# Power.net
KiCad netlist of a schematic drawn in Altium Designer
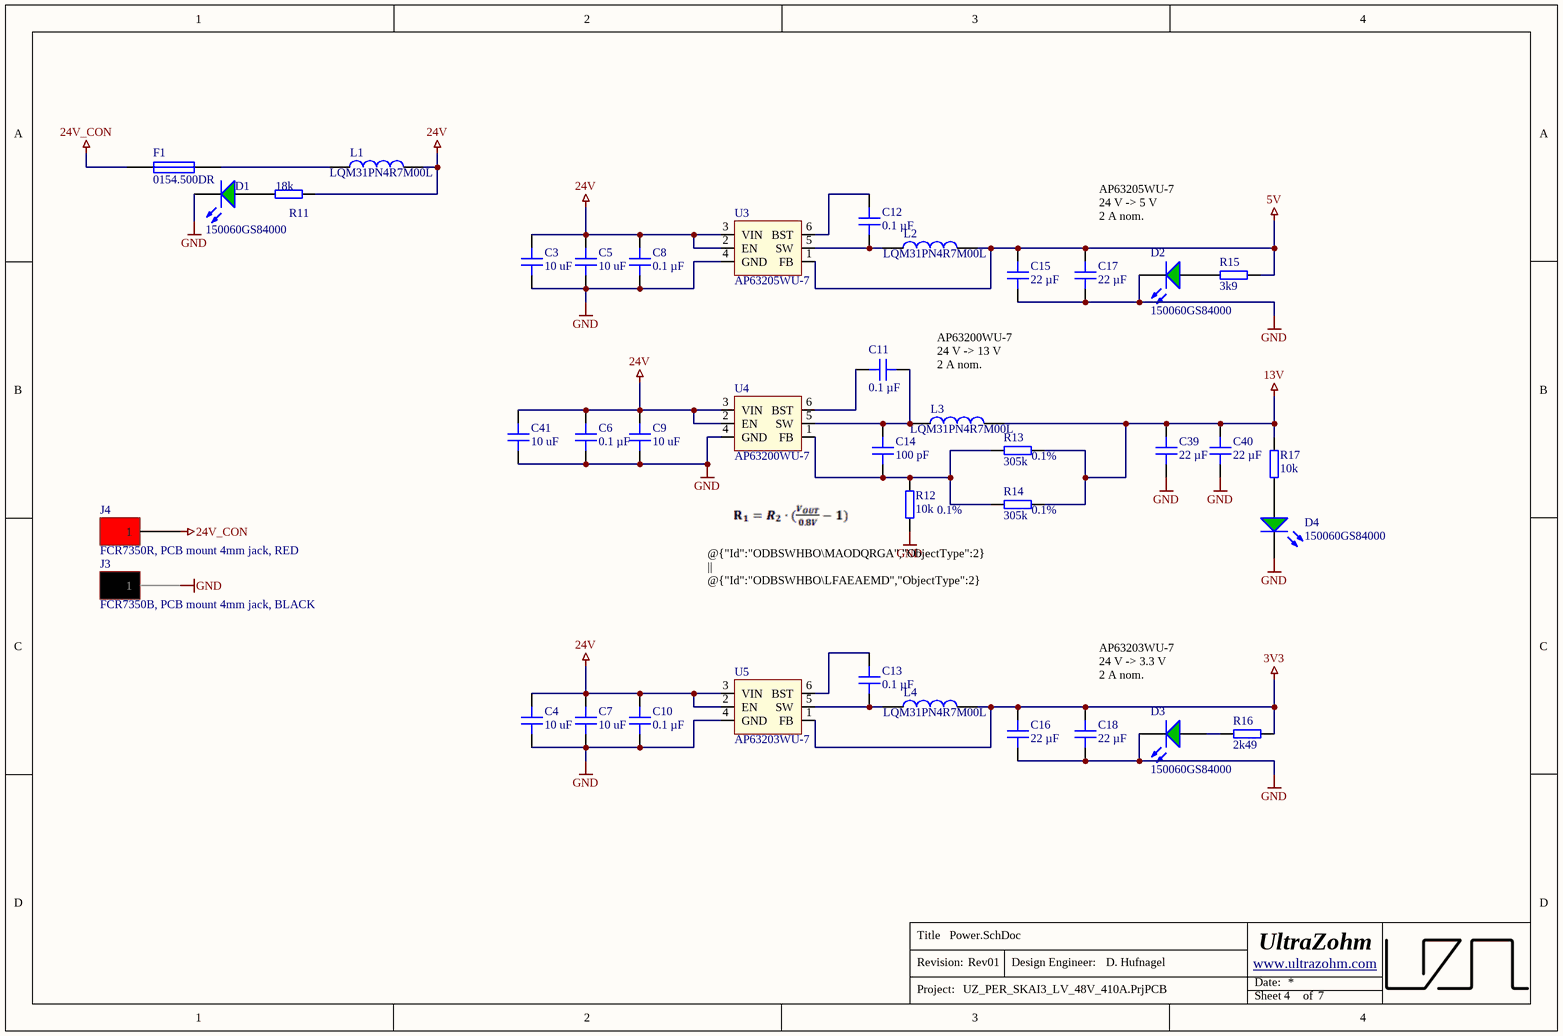
[diagram p0: Power.SchDoc]

(export (version "E")
  (design (tool "Eeschema 10.0.6"))
  (components
    (comp (ref "C3")
      (value "10 uF")
      (footprint "C_1206")
      (description "50V 10uF X7R ±10% 1206  Multilayer Ceramic Capacitors MLCC - SMD/SMT ROHS")
      (fields
        (field (name "MANUFACTURER PART NUMBER") "CL31B106KBHNNNE")
        (field (name "MANUFACTURER") "Samsung Electro-Mechanics")
        (field (name "CREATED FROM") "AGeiger")
      )
      (libsource (lib "user") (part "Capacitor"))
    )
    (comp (ref "C4")
      (value "10 uF")
      (footprint "C_1206")
      (description "50V 10uF X7R ±10% 1206  Multilayer Ceramic Capacitors MLCC - SMD/SMT ROHS")
      (fields
        (field (name "MANUFACTURER PART NUMBER") "CL31B106KBHNNNE")
        (field (name "MANUFACTURER") "Samsung Electro-Mechanics")
        (field (name "CREATED FROM") "AGeiger")
      )
      (libsource (lib "user") (part "Capacitor"))
    )
    (comp (ref "C5")
      (value "10 uF")
      (footprint "C_1206")
      (description "50V 10uF X7R ±10% 1206  Multilayer Ceramic Capacitors MLCC - SMD/SMT ROHS")
      (fields
        (field (name "MANUFACTURER PART NUMBER") "CL31B106KBHNNNE")
        (field (name "MANUFACTURER") "Samsung Electro-Mechanics")
        (field (name "CREATED FROM") "AGeiger")
      )
      (libsource (lib "user") (part "Capacitor"))
    )
    (comp (ref "C6")
      (value "0.1 µF")
      (footprint "C_0603")
      (description "Capacitor 0603, 50 VDC, 0.1 µF, X7R")
      (fields
        (field (name "MANUFACTURER PART NUMBER") "C0603X104K5RAC7411")
        (field (name "MANUFACTURER") "KEMET")
        (field (name "CREATED FROM") "MGremer")
      )
      (libsource (lib "user") (part "Capacitor"))
    )
    (comp (ref "C7")
      (value "10 uF")
      (footprint "C_1206")
      (description "50V 10uF X7R ±10% 1206  Multilayer Ceramic Capacitors MLCC - SMD/SMT ROHS")
      (fields
        (field (name "MANUFACTURER PART NUMBER") "CL31B106KBHNNNE")
        (field (name "MANUFACTURER") "Samsung Electro-Mechanics")
        (field (name "CREATED FROM") "AGeiger")
      )
      (libsource (lib "user") (part "Capacitor"))
    )
    (comp (ref "C8")
      (value "0.1 µF")
      (footprint "C_0603")
      (description "Capacitor 0603, 50 VDC, 0.1 µF, X7R")
      (fields
        (field (name "MANUFACTURER PART NUMBER") "C0603X104K5RAC7411")
        (field (name "MANUFACTURER") "KEMET")
        (field (name "CREATED FROM") "MGremer")
      )
      (libsource (lib "user") (part "Capacitor"))
    )
    (comp (ref "C9")
      (value "10 uF")
      (footprint "C_1206")
      (description "50V 10uF X7R ±10% 1206  Multilayer Ceramic Capacitors MLCC - SMD/SMT ROHS")
      (fields
        (field (name "MANUFACTURER PART NUMBER") "CL31B106KBHNNNE")
        (field (name "MANUFACTURER") "Samsung Electro-Mechanics")
        (field (name "CREATED FROM") "AGeiger")
      )
      (libsource (lib "user") (part "Capacitor"))
    )
    (comp (ref "C10")
      (value "0.1 µF")
      (footprint "C_0603")
      (description "Capacitor 0603, 50 VDC, 0.1 µF, X7R")
      (fields
        (field (name "MANUFACTURER PART NUMBER") "C0603X104K5RAC7411")
        (field (name "MANUFACTURER") "KEMET")
        (field (name "CREATED FROM") "MGremer")
      )
      (libsource (lib "user") (part "Capacitor"))
    )
    (comp (ref "C11")
      (value "0.1 µF")
      (footprint "C_0603")
      (description "Capacitor 0603, 50 VDC, 0.1 µF, X7R")
      (fields
        (field (name "MANUFACTURER PART NUMBER") "C0603X104K5RAC7411")
        (field (name "MANUFACTURER") "KEMET")
        (field (name "CREATED FROM") "MGremer")
      )
      (libsource (lib "user") (part "Capacitor"))
    )
    (comp (ref "C12")
      (value "0.1 µF")
      (footprint "C_0603")
      (description "Capacitor 0603, 50 VDC, 0.1 µF, X7R")
      (fields
        (field (name "MANUFACTURER PART NUMBER") "C0603X104K5RAC7411")
        (field (name "MANUFACTURER") "KEMET")
        (field (name "CREATED FROM") "MGremer")
      )
      (libsource (lib "user") (part "Capacitor"))
    )
    (comp (ref "C13")
      (value "0.1 µF")
      (footprint "C_0603")
      (description "Capacitor 0603, 50 VDC, 0.1 µF, X7R")
      (fields
        (field (name "MANUFACTURER PART NUMBER") "C0603X104K5RAC7411")
        (field (name "MANUFACTURER") "KEMET")
        (field (name "CREATED FROM") "MGremer")
      )
      (libsource (lib "user") (part "Capacitor"))
    )
    (comp (ref "C14")
      (value "100 pF")
      (footprint "C_0603")
      (description "50V 100pF C0G ±5% 0603 Multilayer Ceramic Capacitors MLCC - SMD/SMT ROHS")
      (fields
        (field (name "MANUFACTURER PART NUMBER") "CL10C101JB8NNNC")
        (field (name "MANUFACTURER") "Samsung Electro-Mechanics")
        (field (name "CREATED FROM") "AGeiger")
      )
      (libsource (lib "user") (part "Capacitor"))
    )
    (comp (ref "C15")
      (value "22 µF")
      (footprint "C_0805")
      (description "Capacitor 0805, 25 VDC, 22 µF, X5R")
      (fields
        (field (name "MANUFACTURER PART NUMBER") "GRT21BR61E226ME13L")
        (field (name "MANUFACTURER") "muRata")
        (field (name "CREATED FROM") "MGremer")
      )
      (libsource (lib "user") (part "Capacitor"))
    )
    (comp (ref "C16")
      (value "22 µF")
      (footprint "C_0805")
      (description "Capacitor 0805, 25 VDC, 22 µF, X5R")
      (fields
        (field (name "MANUFACTURER PART NUMBER") "GRT21BR61E226ME13L")
        (field (name "MANUFACTURER") "muRata")
        (field (name "CREATED FROM") "MGremer")
      )
      (libsource (lib "user") (part "Capacitor"))
    )
    (comp (ref "C17")
      (value "22 µF")
      (footprint "C_0805")
      (description "Capacitor 0805, 25 VDC, 22 µF, X5R")
      (fields
        (field (name "MANUFACTURER PART NUMBER") "GRT21BR61E226ME13L")
        (field (name "MANUFACTURER") "muRata")
        (field (name "CREATED FROM") "MGremer")
      )
      (libsource (lib "user") (part "Capacitor"))
    )
    (comp (ref "C18")
      (value "22 µF")
      (footprint "C_0805")
      (description "Capacitor 0805, 25 VDC, 22 µF, X5R")
      (fields
        (field (name "MANUFACTURER PART NUMBER") "GRT21BR61E226ME13L")
        (field (name "MANUFACTURER") "muRata")
        (field (name "CREATED FROM") "MGremer")
      )
      (libsource (lib "user") (part "Capacitor"))
    )
    (comp (ref "C39")
      (value "22 µF")
      (footprint "C_0805")
      (description "Capacitor 0805, 25 VDC, 22 µF, X5R")
      (fields
        (field (name "MANUFACTURER PART NUMBER") "GRT21BR61E226ME13L")
        (field (name "MANUFACTURER") "muRata")
        (field (name "CREATED FROM") "MGremer")
      )
      (libsource (lib "user") (part "Capacitor"))
    )
    (comp (ref "C40")
      (value "22 µF")
      (footprint "C_0805")
      (description "Capacitor 0805, 25 VDC, 22 µF, X5R")
      (fields
        (field (name "MANUFACTURER PART NUMBER") "GRT21BR61E226ME13L")
        (field (name "MANUFACTURER") "muRata")
        (field (name "CREATED FROM") "MGremer")
      )
      (libsource (lib "user") (part "Capacitor"))
    )
    (comp (ref "C41")
      (value "10 uF")
      (footprint "C_1206")
      (description "50V 10uF X7R ±10% 1206  Multilayer Ceramic Capacitors MLCC - SMD/SMT ROHS")
      (fields
        (field (name "MANUFACTURER PART NUMBER") "CL31B106KBHNNNE")
        (field (name "MANUFACTURER") "Samsung Electro-Mechanics")
        (field (name "CREATED FROM") "AGeiger")
      )
      (libsource (lib "user") (part "Capacitor"))
    )
    (comp (ref "D1")
      (value "150060GS84000")
      (footprint "WL-SMCW_0603")
      (description "WL-SMCW SMD Mono-color Chip LED Waterclear Green")
      (fields (field (name "MANUFACTURER") "Wuerth Elektronik") (field (name "CREATED FROM") "MGremer"))
      (libsource (lib "user") (part "LED_Green"))
    )
    (comp (ref "D2")
      (value "150060GS84000")
      (footprint "WL-SMCW_0603")
      (description "WL-SMCW SMD Mono-color Chip LED Waterclear Green")
      (fields (field (name "MANUFACTURER") "Wuerth Elektronik") (field (name "CREATED FROM") "MGremer"))
      (libsource (lib "user") (part "LED_Green"))
    )
    (comp (ref "D3")
      (value "150060GS84000")
      (footprint "WL-SMCW_0603")
      (description "WL-SMCW SMD Mono-color Chip LED Waterclear Green")
      (fields (field (name "MANUFACTURER") "Wuerth Elektronik") (field (name "CREATED FROM") "MGremer"))
      (libsource (lib "user") (part "LED_Green"))
    )
    (comp (ref "D4")
      (value "150060GS84000")
      (footprint "WL-SMCW_0603")
      (description "WL-SMCW SMD Mono-color Chip LED Waterclear Green")
      (fields (field (name "MANUFACTURER") "Wuerth Elektronik") (field (name "CREATED FROM") "MGremer"))
      (libsource (lib "user") (part "LED_Green"))
    )
    (comp (ref "F1")
      (value "0154.500DR")
      (footprint "Littlefuse_154")
      (description "Fuse OMNI BLOK 154")
      (fields (field (name "MANUFACTURER") "Littlefuse") (field (name "CREATED FROM") "MGremer"))
      (libsource (lib "user") (part "Fuse Littelfuse 154 Fuse"))
    )
    (comp (ref "J3")
      (value "FCR7350B, PCB mount 4mm jack, BLACK")
      (footprint "FCR7350")
      (description "FCR7350B, 1000V, 24A, BLACK")
      (fields
        (field (name "MANUFACTURER PART NUMBER") "FCR7350B")
        (field (name "MANUFACTURER") "Cliff")
        (field (name "CREATED FROM") "DHufnagel")
      )
      (libsource (lib "user") (part "FCR7350B"))
    )
    (comp (ref "J4")
      (value "FCR7350R, PCB mount 4mm jack, RED")
      (footprint "FCR7350")
      (description "FCR7350B, 1000V, 24A, RED")
      (fields
        (field (name "MANUFACTURER PART NUMBER") "FCR7350R")
        (field (name "MANUFACTURER") "Cliff")
        (field (name "CREATED FROM") "DHufnagel")
      )
      (libsource (lib "user") (part "FCR7350R"))
    )
    (comp (ref "L1")
      (value "LQM31PN4R7M00L")
      (footprint "IND 1206_3216")
      (description "Power Inductors - SMD 4.7 UH 20%")
      (fields
        (field (name "MF") "EPCOS / TDK")
        (field (name "MPN") "B82464G4154M")
        (field (name "CREATED FROM") "VStarost")
      )
      (libsource (lib "user") (part "B82464G4154M"))
    )
    (comp (ref "L2")
      (value "LQM31PN4R7M00L")
      (footprint "IND 1206_3216")
      (description "Power Inductors - SMD 4.7 UH 20%")
      (fields
        (field (name "MF") "EPCOS / TDK")
        (field (name "MPN") "B82464G4154M")
        (field (name "CREATED FROM") "VStarost")
      )
      (libsource (lib "user") (part "B82464G4154M"))
    )
    (comp (ref "L3")
      (value "LQM31PN4R7M00L")
      (footprint "IND 1206_3216")
      (description "Power Inductors - SMD 4.7 UH 20%")
      (fields
        (field (name "MF") "EPCOS / TDK")
        (field (name "MPN") "B82464G4154M")
        (field (name "CREATED FROM") "VStarost")
      )
      (libsource (lib "user") (part "B82464G4154M"))
    )
    (comp (ref "L4")
      (value "LQM31PN4R7M00L")
      (footprint "IND 1206_3216")
      (description "Power Inductors - SMD 4.7 UH 20%")
      (fields
        (field (name "MF") "EPCOS / TDK")
        (field (name "MPN") "B82464G4154M")
        (field (name "CREATED FROM") "VStarost")
      )
      (libsource (lib "user") (part "B82464G4154M"))
    )
    (comp (ref "R11")
      (value "18k")
      (footprint "RES 0603_1608")
      (description "SMD resistor E24 series")
      (fields
        (field (name "MANUFACTURER PART NUMBER") "RK73B1JTTD183J")
        (field (name "MANUFACTURER") "KOA Speer")
        (field (name "CREATED FROM") "MGremer")
      )
      (libsource (lib "user") (part "Resistor"))
    )
    (comp (ref "R12")
      (value "10k")
      (footprint "RES 0603_1608")
      (description "SMD resistor 0.1%, 10ppm")
      (fields
        (field (name "MANUFACTURER PART NUMBER") "RQ73C1J10KBTD")
        (field (name "MANUFACTURER") "TE Connectivity")
        (field (name "TOLERANCE") "0.1%")
        (field (name "CREATED FROM") "DHufnagel")
      )
      (libsource (lib "user") (part "Resistor"))
    )
    (comp (ref "R13")
      (value "305k")
      (footprint "RES 0603_1608")
      (description "SMD resistor 0.1%")
      (fields
        (field (name "MANUFACTURER PART NUMBER") "RN73R1JTTD3053B25")
        (field (name "MANUFACTURER") "KOA Speer")
        (field (name "TOLERANCE") "0.1%")
        (field (name "CREATED FROM") "DHufnagel")
      )
      (libsource (lib "user") (part "Resistor"))
    )
    (comp (ref "R14")
      (value "305k")
      (footprint "RES 0603_1608")
      (description "SMD resistor 0.1%")
      (fields
        (field (name "MANUFACTURER PART NUMBER") "RN73R1JTTD3053B25")
        (field (name "MANUFACTURER") "KOA Speer")
        (field (name "TOLERANCE") "0.1%")
        (field (name "CREATED FROM") "DHufnagel")
      )
      (libsource (lib "user") (part "Resistor"))
    )
    (comp (ref "R15")
      (value "3k9")
      (footprint "RES 0603_1608")
      (description "SMD resistor E24 series")
      (fields
        (field (name "MANUFACTURER PART NUMBER") "RT0603FRE073K9L")
        (field (name "MANUFACTURER") "YAGEO")
        (field (name "CREATED FROM") "DHufnagel")
      )
      (libsource (lib "user") (part "Resistor"))
    )
    (comp (ref "R16")
      (value "2k49")
      (footprint "RES 0603_1608")
      (description "SMD resistor 1%")
      (fields
        (field (name "MANUFACTURER PART NUMBER") "RC0603FR-072K49L")
        (field (name "MANUFACTURER") "Yageo")
        (field (name "CREATED FROM") "AGeiger")
      )
      (libsource (lib "user") (part "Resistor"))
    )
    (comp (ref "R17")
      (value "10k")
      (footprint "RES 0603_1608")
      (description "SMD resistor 0.1%, 10ppm")
      (fields
        (field (name "MANUFACTURER PART NUMBER") "RQ73C1J10KBTD")
        (field (name "MANUFACTURER") "TE Connectivity")
        (field (name "CREATED FROM") "DHufnagel")
      )
      (libsource (lib "user") (part "Resistor"))
    )
    (comp (ref "U3")
      (value "AP63205WU-7")
      (footprint "TSOT26-6")
      (description "Switching Voltage Regulators DCDC Conv HV Buck TSOT26 T&R 3K")
      (fields (field (name "MANUFACTURER") "Diodes Incorporate") (field (name "CREATED FROM") "VStarost"))
      (libsource (lib "user") (part "AP63205"))
    )
    (comp (ref "U4")
      (value "AP63200WU-7")
      (footprint "TSOT26-6")
      (description "Switching Voltage Regulators DCDC Conv HV Buck TSOT26 T&R 3K")
      (fields (field (name "MANUFACTURER") "Diodes Incorporate") (field (name "CREATED FROM") "VStarost"))
      (libsource (lib "user") (part "AP63205"))
    )
    (comp (ref "U5")
      (value "AP63203WU-7")
      (footprint "TSOT26-6")
      (description "Switching Voltage Regulators DCDC Conv HV Buck TSOT26 T&R 3K")
      (fields
        (field (name "MANUFACTURER") "Diodes Incorporate")
        (field (name "LCSC PART NUMBER") "C780769")
        (field (name "CREATED FROM") "DHufnagel")
      )
      (libsource (lib "user") (part "AP63205"))
    )
  )
  (nets
    (net (code "1") (name "3V3") (class "Default")
      (node (ref "C16") (pin "2") (pinfunction "2_2") (pintype "passive"))
      (node (ref "C18") (pin "2") (pinfunction "2_2") (pintype "passive"))
      (node (ref "L4") (pin "2") (pinfunction "2_2") (pintype "passive"))
      (node (ref "R16") (pin "2") (pinfunction "2_2") (pintype "passive"))
      (node (ref "U5") (pin "1") (pinfunction "FB_1") (pintype "passive"))
    )
    (net (code "2") (name "5V") (class "Default")
      (node (ref "C15") (pin "2") (pinfunction "2_2") (pintype "passive"))
      (node (ref "C17") (pin "2") (pinfunction "2_2") (pintype "passive"))
      (node (ref "L2") (pin "2") (pinfunction "2_2") (pintype "passive"))
      (node (ref "R15") (pin "2") (pinfunction "2_2") (pintype "passive"))
      (node (ref "U3") (pin "1") (pinfunction "FB_1") (pintype "passive"))
    )
    (net (code "3") (name "13V") (class "Default")
      (node (ref "C39") (pin "2") (pinfunction "2_2") (pintype "passive"))
      (node (ref "C40") (pin "2") (pinfunction "2_2") (pintype "passive"))
      (node (ref "L3") (pin "2") (pinfunction "2_2") (pintype "passive"))
      (node (ref "R13") (pin "2") (pinfunction "2_2") (pintype "passive"))
      (node (ref "R14") (pin "2") (pinfunction "2_2") (pintype "passive"))
      (node (ref "R17") (pin "2") (pinfunction "2_2") (pintype "passive"))
    )
    (net (code "4") (name "24V") (class "Default")
      (node (ref "C10") (pin "2") (pinfunction "2_2") (pintype "passive"))
      (node (ref "C3") (pin "2") (pinfunction "2_2") (pintype "passive"))
      (node (ref "C4") (pin "2") (pinfunction "2_2") (pintype "passive"))
      (node (ref "C41") (pin "2") (pinfunction "2_2") (pintype "passive"))
      (node (ref "C5") (pin "2") (pinfunction "2_2") (pintype "passive"))
      (node (ref "C6") (pin "2") (pinfunction "2_2") (pintype "passive"))
      (node (ref "C7") (pin "2") (pinfunction "2_2") (pintype "passive"))
      (node (ref "C8") (pin "2") (pinfunction "2_2") (pintype "passive"))
      (node (ref "C9") (pin "2") (pinfunction "2_2") (pintype "passive"))
      (node (ref "L1") (pin "2") (pinfunction "2_2") (pintype "passive"))
      (node (ref "R11") (pin "2") (pinfunction "2_2") (pintype "passive"))
      (node (ref "U3") (pin "2") (pinfunction "EN_2") (pintype "passive"))
      (node (ref "U3") (pin "3") (pinfunction "VIN_3") (pintype "passive"))
      (node (ref "U4") (pin "2") (pinfunction "EN_2") (pintype "passive"))
      (node (ref "U4") (pin "3") (pinfunction "VIN_3") (pintype "passive"))
      (node (ref "U5") (pin "2") (pinfunction "EN_2") (pintype "passive"))
      (node (ref "U5") (pin "3") (pinfunction "VIN_3") (pintype "passive"))
    )
    (net (code "5") (name "24V_CON") (class "Default")
      (node (ref "F1") (pin "1") (pinfunction "1_1") (pintype "passive"))
      (node (ref "J4") (pin "1") (pinfunction "1_1") (pintype "passive"))
    )
    (net (code "6") (name "GND") (class "Default")
      (node (ref "C10") (pin "1") (pinfunction "1_1") (pintype "passive"))
      (node (ref "C15") (pin "1") (pinfunction "1_1") (pintype "passive"))
      (node (ref "C16") (pin "1") (pinfunction "1_1") (pintype "passive"))
      (node (ref "C17") (pin "1") (pinfunction "1_1") (pintype "passive"))
      (node (ref "C18") (pin "1") (pinfunction "1_1") (pintype "passive"))
      (node (ref "C3") (pin "1") (pinfunction "1_1") (pintype "passive"))
      (node (ref "C39") (pin "1") (pinfunction "1_1") (pintype "passive"))
      (node (ref "C4") (pin "1") (pinfunction "1_1") (pintype "passive"))
      (node (ref "C40") (pin "1") (pinfunction "1_1") (pintype "passive"))
      (node (ref "C41") (pin "1") (pinfunction "1_1") (pintype "passive"))
      (node (ref "C5") (pin "1") (pinfunction "1_1") (pintype "passive"))
      (node (ref "C6") (pin "1") (pinfunction "1_1") (pintype "passive"))
      (node (ref "C7") (pin "1") (pinfunction "1_1") (pintype "passive"))
      (node (ref "C8") (pin "1") (pinfunction "1_1") (pintype "passive"))
      (node (ref "C9") (pin "1") (pinfunction "1_1") (pintype "passive"))
      (node (ref "D1") (pin "1") (pinfunction "K_1") (pintype "passive"))
      (node (ref "D2") (pin "1") (pinfunction "K_1") (pintype "passive"))
      (node (ref "D3") (pin "1") (pinfunction "K_1") (pintype "passive"))
      (node (ref "D4") (pin "1") (pinfunction "K_1") (pintype "passive"))
      (node (ref "J3") (pin "1") (pinfunction "1_1") (pintype "passive"))
      (node (ref "R12") (pin "1") (pinfunction "1_1") (pintype "passive"))
      (node (ref "U3") (pin "4") (pinfunction "GND_4") (pintype "passive"))
      (node (ref "U4") (pin "4") (pinfunction "GND_4") (pintype "passive"))
      (node (ref "U5") (pin "4") (pinfunction "GND_4") (pintype "passive"))
    )
    (net (code "7") (name "Net-(D1-A)") (class "Default")
      (node (ref "D1") (pin "2") (pinfunction "A_2") (pintype "passive"))
      (node (ref "R11") (pin "1") (pinfunction "1_1") (pintype "passive"))
    )
    (net (code "8") (name "Net-(D2-A)") (class "Default")
      (node (ref "D2") (pin "2") (pinfunction "A_2") (pintype "passive"))
      (node (ref "R15") (pin "1") (pinfunction "1_1") (pintype "passive"))
    )
    (net (code "9") (name "Net-(D3-A)") (class "Default")
      (node (ref "D3") (pin "2") (pinfunction "A_2") (pintype "passive"))
      (node (ref "R16") (pin "1") (pinfunction "1_1") (pintype "passive"))
    )
    (net (code "10") (name "Net-(D4-A)") (class "Default")
      (node (ref "D4") (pin "2") (pinfunction "A_2") (pintype "passive"))
      (node (ref "R17") (pin "1") (pinfunction "1_1") (pintype "passive"))
    )
    (net (code "11") (name "Net-(F1-Pad2)") (class "Default")
      (node (ref "F1") (pin "2") (pinfunction "2_2") (pintype "passive"))
      (node (ref "L1") (pin "1") (pinfunction "1_1") (pintype "passive"))
    )
    (net (code "12") (name "Net-(U3-BST)") (class "Default")
      (node (ref "C12") (pin "2") (pinfunction "2_2") (pintype "passive"))
      (node (ref "U3") (pin "6") (pinfunction "BST_6") (pintype "passive"))
    )
    (net (code "13") (name "Net-(U3-SW)") (class "Default")
      (node (ref "C12") (pin "1") (pinfunction "1_1") (pintype "passive"))
      (node (ref "L2") (pin "1") (pinfunction "1_1") (pintype "passive"))
      (node (ref "U3") (pin "5") (pinfunction "SW_5") (pintype "passive"))
    )
    (net (code "14") (name "Net-(U4-BST)") (class "Default")
      (node (ref "C11") (pin "2") (pinfunction "2_2") (pintype "passive"))
      (node (ref "U4") (pin "6") (pinfunction "BST_6") (pintype "passive"))
    )
    (net (code "15") (name "Net-(U4-FB)") (class "Default")
      (node (ref "C14") (pin "1") (pinfunction "1_1") (pintype "passive"))
      (node (ref "R12") (pin "2") (pinfunction "2_2") (pintype "passive"))
      (node (ref "R13") (pin "1") (pinfunction "1_1") (pintype "passive"))
      (node (ref "R14") (pin "1") (pinfunction "1_1") (pintype "passive"))
      (node (ref "U4") (pin "1") (pinfunction "FB_1") (pintype "passive"))
    )
    (net (code "16") (name "Net-(U4-SW)") (class "Default")
      (node (ref "C11") (pin "1") (pinfunction "1_1") (pintype "passive"))
      (node (ref "C14") (pin "2") (pinfunction "2_2") (pintype "passive"))
      (node (ref "L3") (pin "1") (pinfunction "1_1") (pintype "passive"))
      (node (ref "U4") (pin "5") (pinfunction "SW_5") (pintype "passive"))
    )
    (net (code "17") (name "Net-(U5-BST)") (class "Default")
      (node (ref "C13") (pin "2") (pinfunction "2_2") (pintype "passive"))
      (node (ref "U5") (pin "6") (pinfunction "BST_6") (pintype "passive"))
    )
    (net (code "18") (name "Net-(U5-SW)") (class "Default")
      (node (ref "C13") (pin "1") (pinfunction "1_1") (pintype "passive"))
      (node (ref "L4") (pin "1") (pinfunction "1_1") (pintype "passive"))
      (node (ref "U5") (pin "5") (pinfunction "SW_5") (pintype "passive"))
    )
  )
)
